# SCH_LED_stick_2021-12-25.net
KiCad netlist of a schematic drawn in EasyEDA
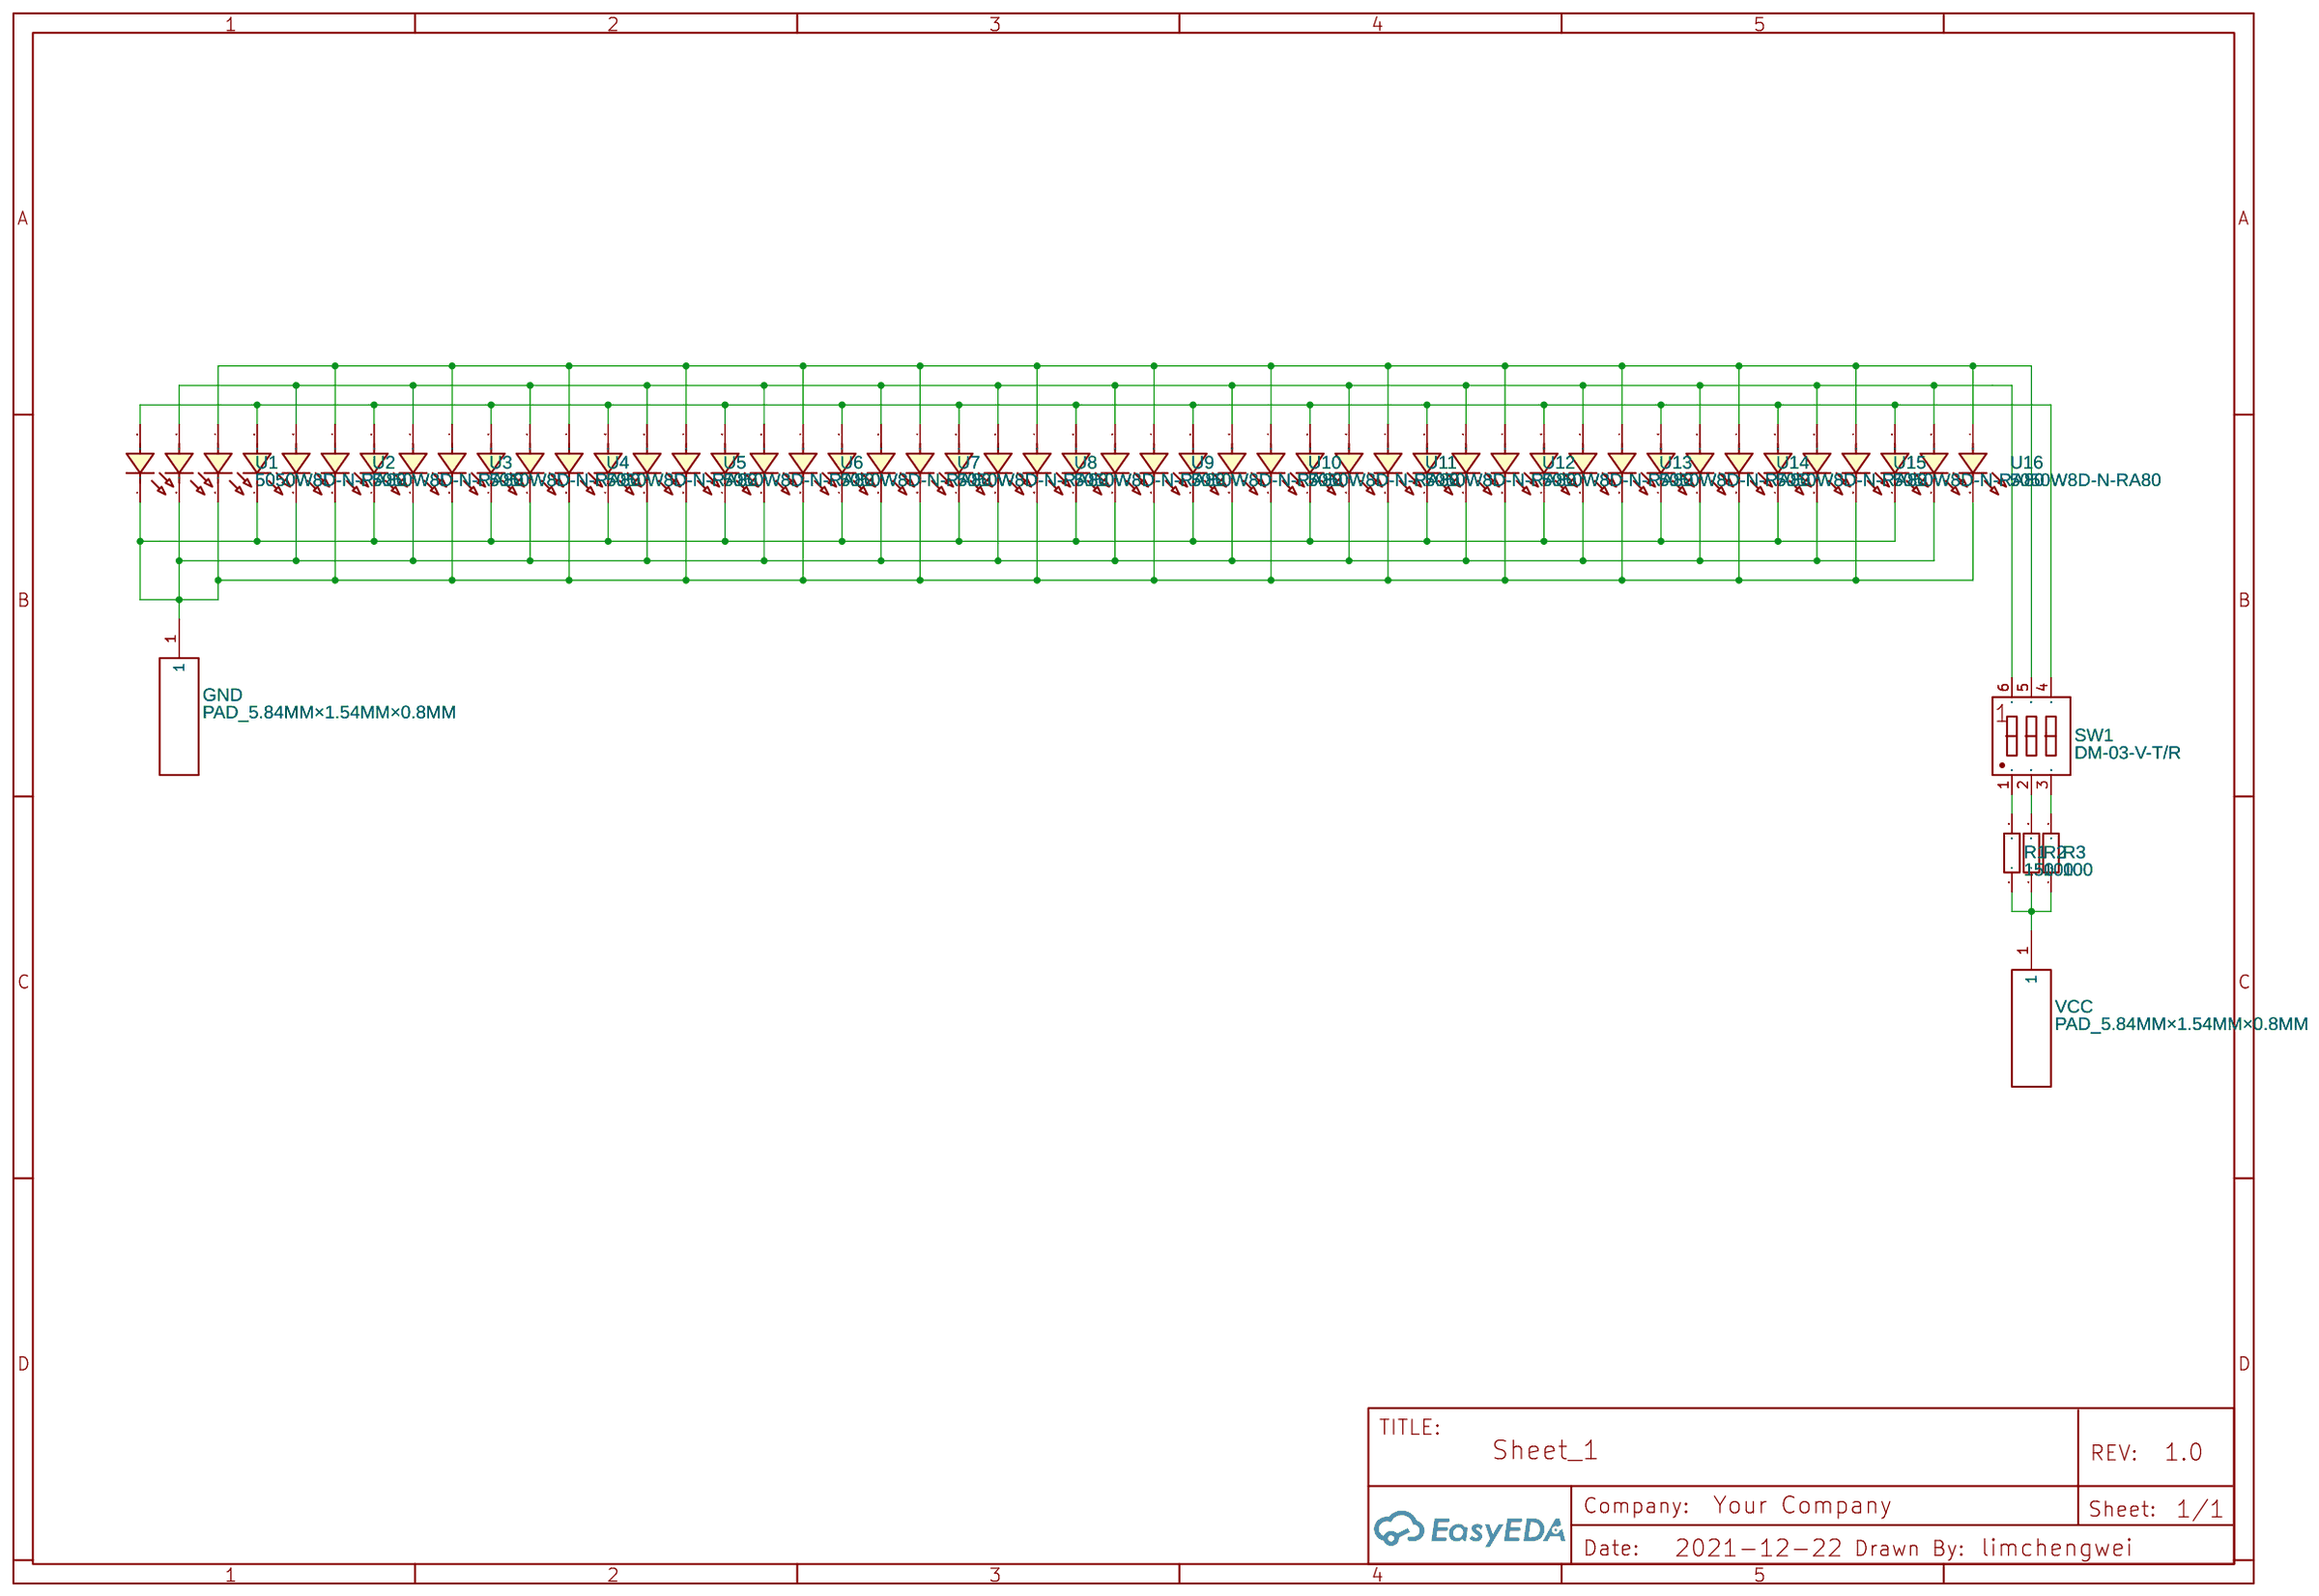
[diagram p0: schematic sheet]

(export (version "E")
  (design (tool "Eeschema 10.0.6"))
  (components
    (comp (ref "GND")
      (value "PAD_5.84MM×1.54MM×0.8MM")
      (fields
        (field (name "BOM_Manufacturer Part") "PAD_5.84mm×1.54mm×0.8mm")
        (field (name "BOM_Supplier Part") "C9900000335")
      )
      (libsource (lib "") (part "PAD_5.84MM×1.54MM×0.8MM_1"))
    )
    (comp (ref "R1")
      (value "150")
      (fields
        (field (name "BOM_Manufacturer Part") "AECR1210F220RK9")
        (field (name "BOM_Supplier Part") "C351971")
      )
      (libsource (lib "") (part "AECR1210F220RK9"))
    )
    (comp (ref "R2")
      (value "100")
      (fields
        (field (name "BOM_Manufacturer Part") "AECR1210F220RK9")
        (field (name "BOM_Supplier Part") "C351971")
      )
      (libsource (lib "") (part "AECR1210F220RK9"))
    )
    (comp (ref "R3")
      (value "100")
      (fields
        (field (name "BOM_Manufacturer Part") "AECR1210F220RK9")
        (field (name "BOM_Supplier Part") "C351971")
      )
      (libsource (lib "") (part "AECR1210F220RK9"))
    )
    (comp (ref "SW1")
      (value "DM-03-V-T/R")
      (fields (field (name "BOM_Supplier Part") "C501631"))
      (libsource (lib "") (part "DM-03-V-T/R"))
    )
    (comp (ref "U1")
      (value "5050W8D-N-RA80")
      (fields
        (field (name "BOM_Manufacturer Part") "5050W8D-N-Ra80")
        (field (name "BOM_Supplier Part") "C2842550")
      )
      (libsource (lib "") (part "5050W8D-N-RA80"))
    )
    (comp (ref "U2")
      (value "5050W8D-N-RA80")
      (fields
        (field (name "BOM_Manufacturer Part") "5050W8D-N-Ra80")
        (field (name "BOM_Supplier Part") "C2842550")
      )
      (libsource (lib "") (part "5050W8D-N-RA80"))
    )
    (comp (ref "U3")
      (value "5050W8D-N-RA80")
      (fields
        (field (name "BOM_Manufacturer Part") "5050W8D-N-Ra80")
        (field (name "BOM_Supplier Part") "C2842550")
      )
      (libsource (lib "") (part "5050W8D-N-RA80"))
    )
    (comp (ref "U4")
      (value "5050W8D-N-RA80")
      (fields
        (field (name "BOM_Manufacturer Part") "5050W8D-N-Ra80")
        (field (name "BOM_Supplier Part") "C2842550")
      )
      (libsource (lib "") (part "5050W8D-N-RA80"))
    )
    (comp (ref "U5")
      (value "5050W8D-N-RA80")
      (fields
        (field (name "BOM_Manufacturer Part") "5050W8D-N-Ra80")
        (field (name "BOM_Supplier Part") "C2842550")
      )
      (libsource (lib "") (part "5050W8D-N-RA80"))
    )
    (comp (ref "U6")
      (value "5050W8D-N-RA80")
      (fields
        (field (name "BOM_Manufacturer Part") "5050W8D-N-Ra80")
        (field (name "BOM_Supplier Part") "C2842550")
      )
      (libsource (lib "") (part "5050W8D-N-RA80"))
    )
    (comp (ref "U7")
      (value "5050W8D-N-RA80")
      (fields
        (field (name "BOM_Manufacturer Part") "5050W8D-N-Ra80")
        (field (name "BOM_Supplier Part") "C2842550")
      )
      (libsource (lib "") (part "5050W8D-N-RA80"))
    )
    (comp (ref "U8")
      (value "5050W8D-N-RA80")
      (fields
        (field (name "BOM_Manufacturer Part") "5050W8D-N-Ra80")
        (field (name "BOM_Supplier Part") "C2842550")
      )
      (libsource (lib "") (part "5050W8D-N-RA80"))
    )
    (comp (ref "U9")
      (value "5050W8D-N-RA80")
      (fields
        (field (name "BOM_Manufacturer Part") "5050W8D-N-Ra80")
        (field (name "BOM_Supplier Part") "C2842550")
      )
      (libsource (lib "") (part "5050W8D-N-RA80"))
    )
    (comp (ref "U10")
      (value "5050W8D-N-RA80")
      (fields
        (field (name "BOM_Manufacturer Part") "5050W8D-N-Ra80")
        (field (name "BOM_Supplier Part") "C2842550")
      )
      (libsource (lib "") (part "5050W8D-N-RA80"))
    )
    (comp (ref "U11")
      (value "5050W8D-N-RA80")
      (fields
        (field (name "BOM_Manufacturer Part") "5050W8D-N-Ra80")
        (field (name "BOM_Supplier Part") "C2842550")
      )
      (libsource (lib "") (part "5050W8D-N-RA80"))
    )
    (comp (ref "U12")
      (value "5050W8D-N-RA80")
      (fields
        (field (name "BOM_Manufacturer Part") "5050W8D-N-Ra80")
        (field (name "BOM_Supplier Part") "C2842550")
      )
      (libsource (lib "") (part "5050W8D-N-RA80"))
    )
    (comp (ref "U13")
      (value "5050W8D-N-RA80")
      (fields
        (field (name "BOM_Manufacturer Part") "5050W8D-N-Ra80")
        (field (name "BOM_Supplier Part") "C2842550")
      )
      (libsource (lib "") (part "5050W8D-N-RA80"))
    )
    (comp (ref "U14")
      (value "5050W8D-N-RA80")
      (fields
        (field (name "BOM_Manufacturer Part") "5050W8D-N-Ra80")
        (field (name "BOM_Supplier Part") "C2842550")
      )
      (libsource (lib "") (part "5050W8D-N-RA80"))
    )
    (comp (ref "U15")
      (value "5050W8D-N-RA80")
      (fields
        (field (name "BOM_Manufacturer Part") "5050W8D-N-Ra80")
        (field (name "BOM_Supplier Part") "C2842550")
      )
      (libsource (lib "") (part "5050W8D-N-RA80"))
    )
    (comp (ref "U16")
      (value "5050W8D-N-RA80")
      (fields
        (field (name "BOM_Manufacturer Part") "5050W8D-N-Ra80")
        (field (name "BOM_Supplier Part") "C2842550")
      )
      (libsource (lib "") (part "5050W8D-N-RA80"))
    )
    (comp (ref "VCC")
      (value "PAD_5.84MM×1.54MM×0.8MM")
      (fields
        (field (name "BOM_Manufacturer Part") "PAD_5.84mm×1.54mm×0.8mm")
        (field (name "BOM_Supplier Part") "C9900000335")
      )
      (libsource (lib "") (part "PAD_5.84MM×1.54MM×0.8MM"))
    )
  )
  (nets
    (net (code "1") (name "Net-(GND-Pad1)") (class "Default")
      (node (ref "GND") (pin "1") (pinfunction "1_1") (pintype "unspecified"))
      (node (ref "U1") (pin "1") (pinfunction "K_1") (pintype "unspecified"))
      (node (ref "U1") (pin "2") (pinfunction "K_2") (pintype "unspecified"))
      (node (ref "U1") (pin "3") (pinfunction "K_3") (pintype "unspecified"))
      (node (ref "U10") (pin "1") (pinfunction "K_1") (pintype "unspecified"))
      (node (ref "U10") (pin "2") (pinfunction "K_2") (pintype "unspecified"))
      (node (ref "U10") (pin "3") (pinfunction "K_3") (pintype "unspecified"))
      (node (ref "U11") (pin "1") (pinfunction "K_1") (pintype "unspecified"))
      (node (ref "U11") (pin "2") (pinfunction "K_2") (pintype "unspecified"))
      (node (ref "U11") (pin "3") (pinfunction "K_3") (pintype "unspecified"))
      (node (ref "U12") (pin "1") (pinfunction "K_1") (pintype "unspecified"))
      (node (ref "U12") (pin "2") (pinfunction "K_2") (pintype "unspecified"))
      (node (ref "U12") (pin "3") (pinfunction "K_3") (pintype "unspecified"))
      (node (ref "U13") (pin "1") (pinfunction "K_1") (pintype "unspecified"))
      (node (ref "U13") (pin "2") (pinfunction "K_2") (pintype "unspecified"))
      (node (ref "U13") (pin "3") (pinfunction "K_3") (pintype "unspecified"))
      (node (ref "U14") (pin "1") (pinfunction "K_1") (pintype "unspecified"))
      (node (ref "U14") (pin "2") (pinfunction "K_2") (pintype "unspecified"))
      (node (ref "U14") (pin "3") (pinfunction "K_3") (pintype "unspecified"))
      (node (ref "U15") (pin "1") (pinfunction "K_1") (pintype "unspecified"))
      (node (ref "U15") (pin "2") (pinfunction "K_2") (pintype "unspecified"))
      (node (ref "U15") (pin "3") (pinfunction "K_3") (pintype "unspecified"))
      (node (ref "U16") (pin "1") (pinfunction "K_1") (pintype "unspecified"))
      (node (ref "U16") (pin "2") (pinfunction "K_2") (pintype "unspecified"))
      (node (ref "U16") (pin "3") (pinfunction "K_3") (pintype "unspecified"))
      (node (ref "U2") (pin "1") (pinfunction "K_1") (pintype "unspecified"))
      (node (ref "U2") (pin "2") (pinfunction "K_2") (pintype "unspecified"))
      (node (ref "U2") (pin "3") (pinfunction "K_3") (pintype "unspecified"))
      (node (ref "U3") (pin "1") (pinfunction "K_1") (pintype "unspecified"))
      (node (ref "U3") (pin "2") (pinfunction "K_2") (pintype "unspecified"))
      (node (ref "U3") (pin "3") (pinfunction "K_3") (pintype "unspecified"))
      (node (ref "U4") (pin "1") (pinfunction "K_1") (pintype "unspecified"))
      (node (ref "U4") (pin "2") (pinfunction "K_2") (pintype "unspecified"))
      (node (ref "U4") (pin "3") (pinfunction "K_3") (pintype "unspecified"))
      (node (ref "U5") (pin "1") (pinfunction "K_1") (pintype "unspecified"))
      (node (ref "U5") (pin "2") (pinfunction "K_2") (pintype "unspecified"))
      (node (ref "U5") (pin "3") (pinfunction "K_3") (pintype "unspecified"))
      (node (ref "U6") (pin "1") (pinfunction "K_1") (pintype "unspecified"))
      (node (ref "U6") (pin "2") (pinfunction "K_2") (pintype "unspecified"))
      (node (ref "U6") (pin "3") (pinfunction "K_3") (pintype "unspecified"))
      (node (ref "U7") (pin "1") (pinfunction "K_1") (pintype "unspecified"))
      (node (ref "U7") (pin "2") (pinfunction "K_2") (pintype "unspecified"))
      (node (ref "U7") (pin "3") (pinfunction "K_3") (pintype "unspecified"))
      (node (ref "U8") (pin "1") (pinfunction "K_1") (pintype "unspecified"))
      (node (ref "U8") (pin "2") (pinfunction "K_2") (pintype "unspecified"))
      (node (ref "U8") (pin "3") (pinfunction "K_3") (pintype "unspecified"))
      (node (ref "U9") (pin "1") (pinfunction "K_1") (pintype "unspecified"))
      (node (ref "U9") (pin "2") (pinfunction "K_2") (pintype "unspecified"))
      (node (ref "U9") (pin "3") (pinfunction "K_3") (pintype "unspecified"))
    )
    (net (code "2") (name "Net-(R1-Pad1)") (class "Default")
      (node (ref "R1") (pin "1") (pinfunction "1_1") (pintype "unspecified"))
      (node (ref "R2") (pin "1") (pinfunction "1_1") (pintype "unspecified"))
      (node (ref "R3") (pin "1") (pinfunction "1_1") (pintype "unspecified"))
      (node (ref "VCC") (pin "1") (pinfunction "1_1") (pintype "unspecified"))
    )
    (net (code "3") (name "Net-(SW1-PIN1)") (class "Default")
      (node (ref "R1") (pin "2") (pinfunction "2_2") (pintype "unspecified"))
      (node (ref "SW1") (pin "1") (pinfunction "PIN1_1") (pintype "unspecified"))
    )
    (net (code "4") (name "Net-(SW1-PIN2)") (class "Default")
      (node (ref "R2") (pin "2") (pinfunction "2_2") (pintype "unspecified"))
      (node (ref "SW1") (pin "2") (pinfunction "PIN2_2") (pintype "unspecified"))
    )
    (net (code "5") (name "Net-(SW1-PIN3)") (class "Default")
      (node (ref "R3") (pin "2") (pinfunction "2_2") (pintype "unspecified"))
      (node (ref "SW1") (pin "3") (pinfunction "PIN3_3") (pintype "unspecified"))
    )
    (net (code "6") (name "Net-(SW1-PIN4)") (class "Default")
      (node (ref "SW1") (pin "4") (pinfunction "PIN4_4") (pintype "unspecified"))
      (node (ref "U1") (pin "6") (pinfunction "A_6") (pintype "unspecified"))
      (node (ref "U10") (pin "6") (pinfunction "A_6") (pintype "unspecified"))
      (node (ref "U11") (pin "6") (pinfunction "A_6") (pintype "unspecified"))
      (node (ref "U12") (pin "6") (pinfunction "A_6") (pintype "unspecified"))
      (node (ref "U13") (pin "6") (pinfunction "A_6") (pintype "unspecified"))
      (node (ref "U14") (pin "6") (pinfunction "A_6") (pintype "unspecified"))
      (node (ref "U15") (pin "6") (pinfunction "A_6") (pintype "unspecified"))
      (node (ref "U16") (pin "6") (pinfunction "A_6") (pintype "unspecified"))
      (node (ref "U2") (pin "6") (pinfunction "A_6") (pintype "unspecified"))
      (node (ref "U3") (pin "6") (pinfunction "A_6") (pintype "unspecified"))
      (node (ref "U4") (pin "6") (pinfunction "A_6") (pintype "unspecified"))
      (node (ref "U5") (pin "6") (pinfunction "A_6") (pintype "unspecified"))
      (node (ref "U6") (pin "6") (pinfunction "A_6") (pintype "unspecified"))
      (node (ref "U7") (pin "6") (pinfunction "A_6") (pintype "unspecified"))
      (node (ref "U8") (pin "6") (pinfunction "A_6") (pintype "unspecified"))
      (node (ref "U9") (pin "6") (pinfunction "A_6") (pintype "unspecified"))
    )
    (net (code "7") (name "Net-(SW1-PIN5)") (class "Default")
      (node (ref "SW1") (pin "5") (pinfunction "PIN5_5") (pintype "unspecified"))
      (node (ref "U1") (pin "4") (pinfunction "A_4") (pintype "unspecified"))
      (node (ref "U10") (pin "4") (pinfunction "A_4") (pintype "unspecified"))
      (node (ref "U11") (pin "4") (pinfunction "A_4") (pintype "unspecified"))
      (node (ref "U12") (pin "4") (pinfunction "A_4") (pintype "unspecified"))
      (node (ref "U13") (pin "4") (pinfunction "A_4") (pintype "unspecified"))
      (node (ref "U14") (pin "4") (pinfunction "A_4") (pintype "unspecified"))
      (node (ref "U15") (pin "4") (pinfunction "A_4") (pintype "unspecified"))
      (node (ref "U16") (pin "4") (pinfunction "A_4") (pintype "unspecified"))
      (node (ref "U2") (pin "4") (pinfunction "A_4") (pintype "unspecified"))
      (node (ref "U3") (pin "4") (pinfunction "A_4") (pintype "unspecified"))
      (node (ref "U4") (pin "4") (pinfunction "A_4") (pintype "unspecified"))
      (node (ref "U5") (pin "4") (pinfunction "A_4") (pintype "unspecified"))
      (node (ref "U6") (pin "4") (pinfunction "A_4") (pintype "unspecified"))
      (node (ref "U7") (pin "4") (pinfunction "A_4") (pintype "unspecified"))
      (node (ref "U8") (pin "4") (pinfunction "A_4") (pintype "unspecified"))
      (node (ref "U9") (pin "4") (pinfunction "A_4") (pintype "unspecified"))
    )
    (net (code "8") (name "Net-(SW1-PIN6)") (class "Default")
      (node (ref "SW1") (pin "6") (pinfunction "PIN6_6") (pintype "unspecified"))
      (node (ref "U1") (pin "5") (pinfunction "A_5") (pintype "unspecified"))
      (node (ref "U10") (pin "5") (pinfunction "A_5") (pintype "unspecified"))
      (node (ref "U11") (pin "5") (pinfunction "A_5") (pintype "unspecified"))
      (node (ref "U12") (pin "5") (pinfunction "A_5") (pintype "unspecified"))
      (node (ref "U13") (pin "5") (pinfunction "A_5") (pintype "unspecified"))
      (node (ref "U14") (pin "5") (pinfunction "A_5") (pintype "unspecified"))
      (node (ref "U15") (pin "5") (pinfunction "A_5") (pintype "unspecified"))
      (node (ref "U16") (pin "5") (pinfunction "A_5") (pintype "unspecified"))
      (node (ref "U2") (pin "5") (pinfunction "A_5") (pintype "unspecified"))
      (node (ref "U3") (pin "5") (pinfunction "A_5") (pintype "unspecified"))
      (node (ref "U4") (pin "5") (pinfunction "A_5") (pintype "unspecified"))
      (node (ref "U5") (pin "5") (pinfunction "A_5") (pintype "unspecified"))
      (node (ref "U6") (pin "5") (pinfunction "A_5") (pintype "unspecified"))
      (node (ref "U7") (pin "5") (pinfunction "A_5") (pintype "unspecified"))
      (node (ref "U8") (pin "5") (pinfunction "A_5") (pintype "unspecified"))
      (node (ref "U9") (pin "5") (pinfunction "A_5") (pintype "unspecified"))
    )
  )
)
